# UV_LED_SH01.net
KiCad netlist of a schematic drawn in EasyEDA
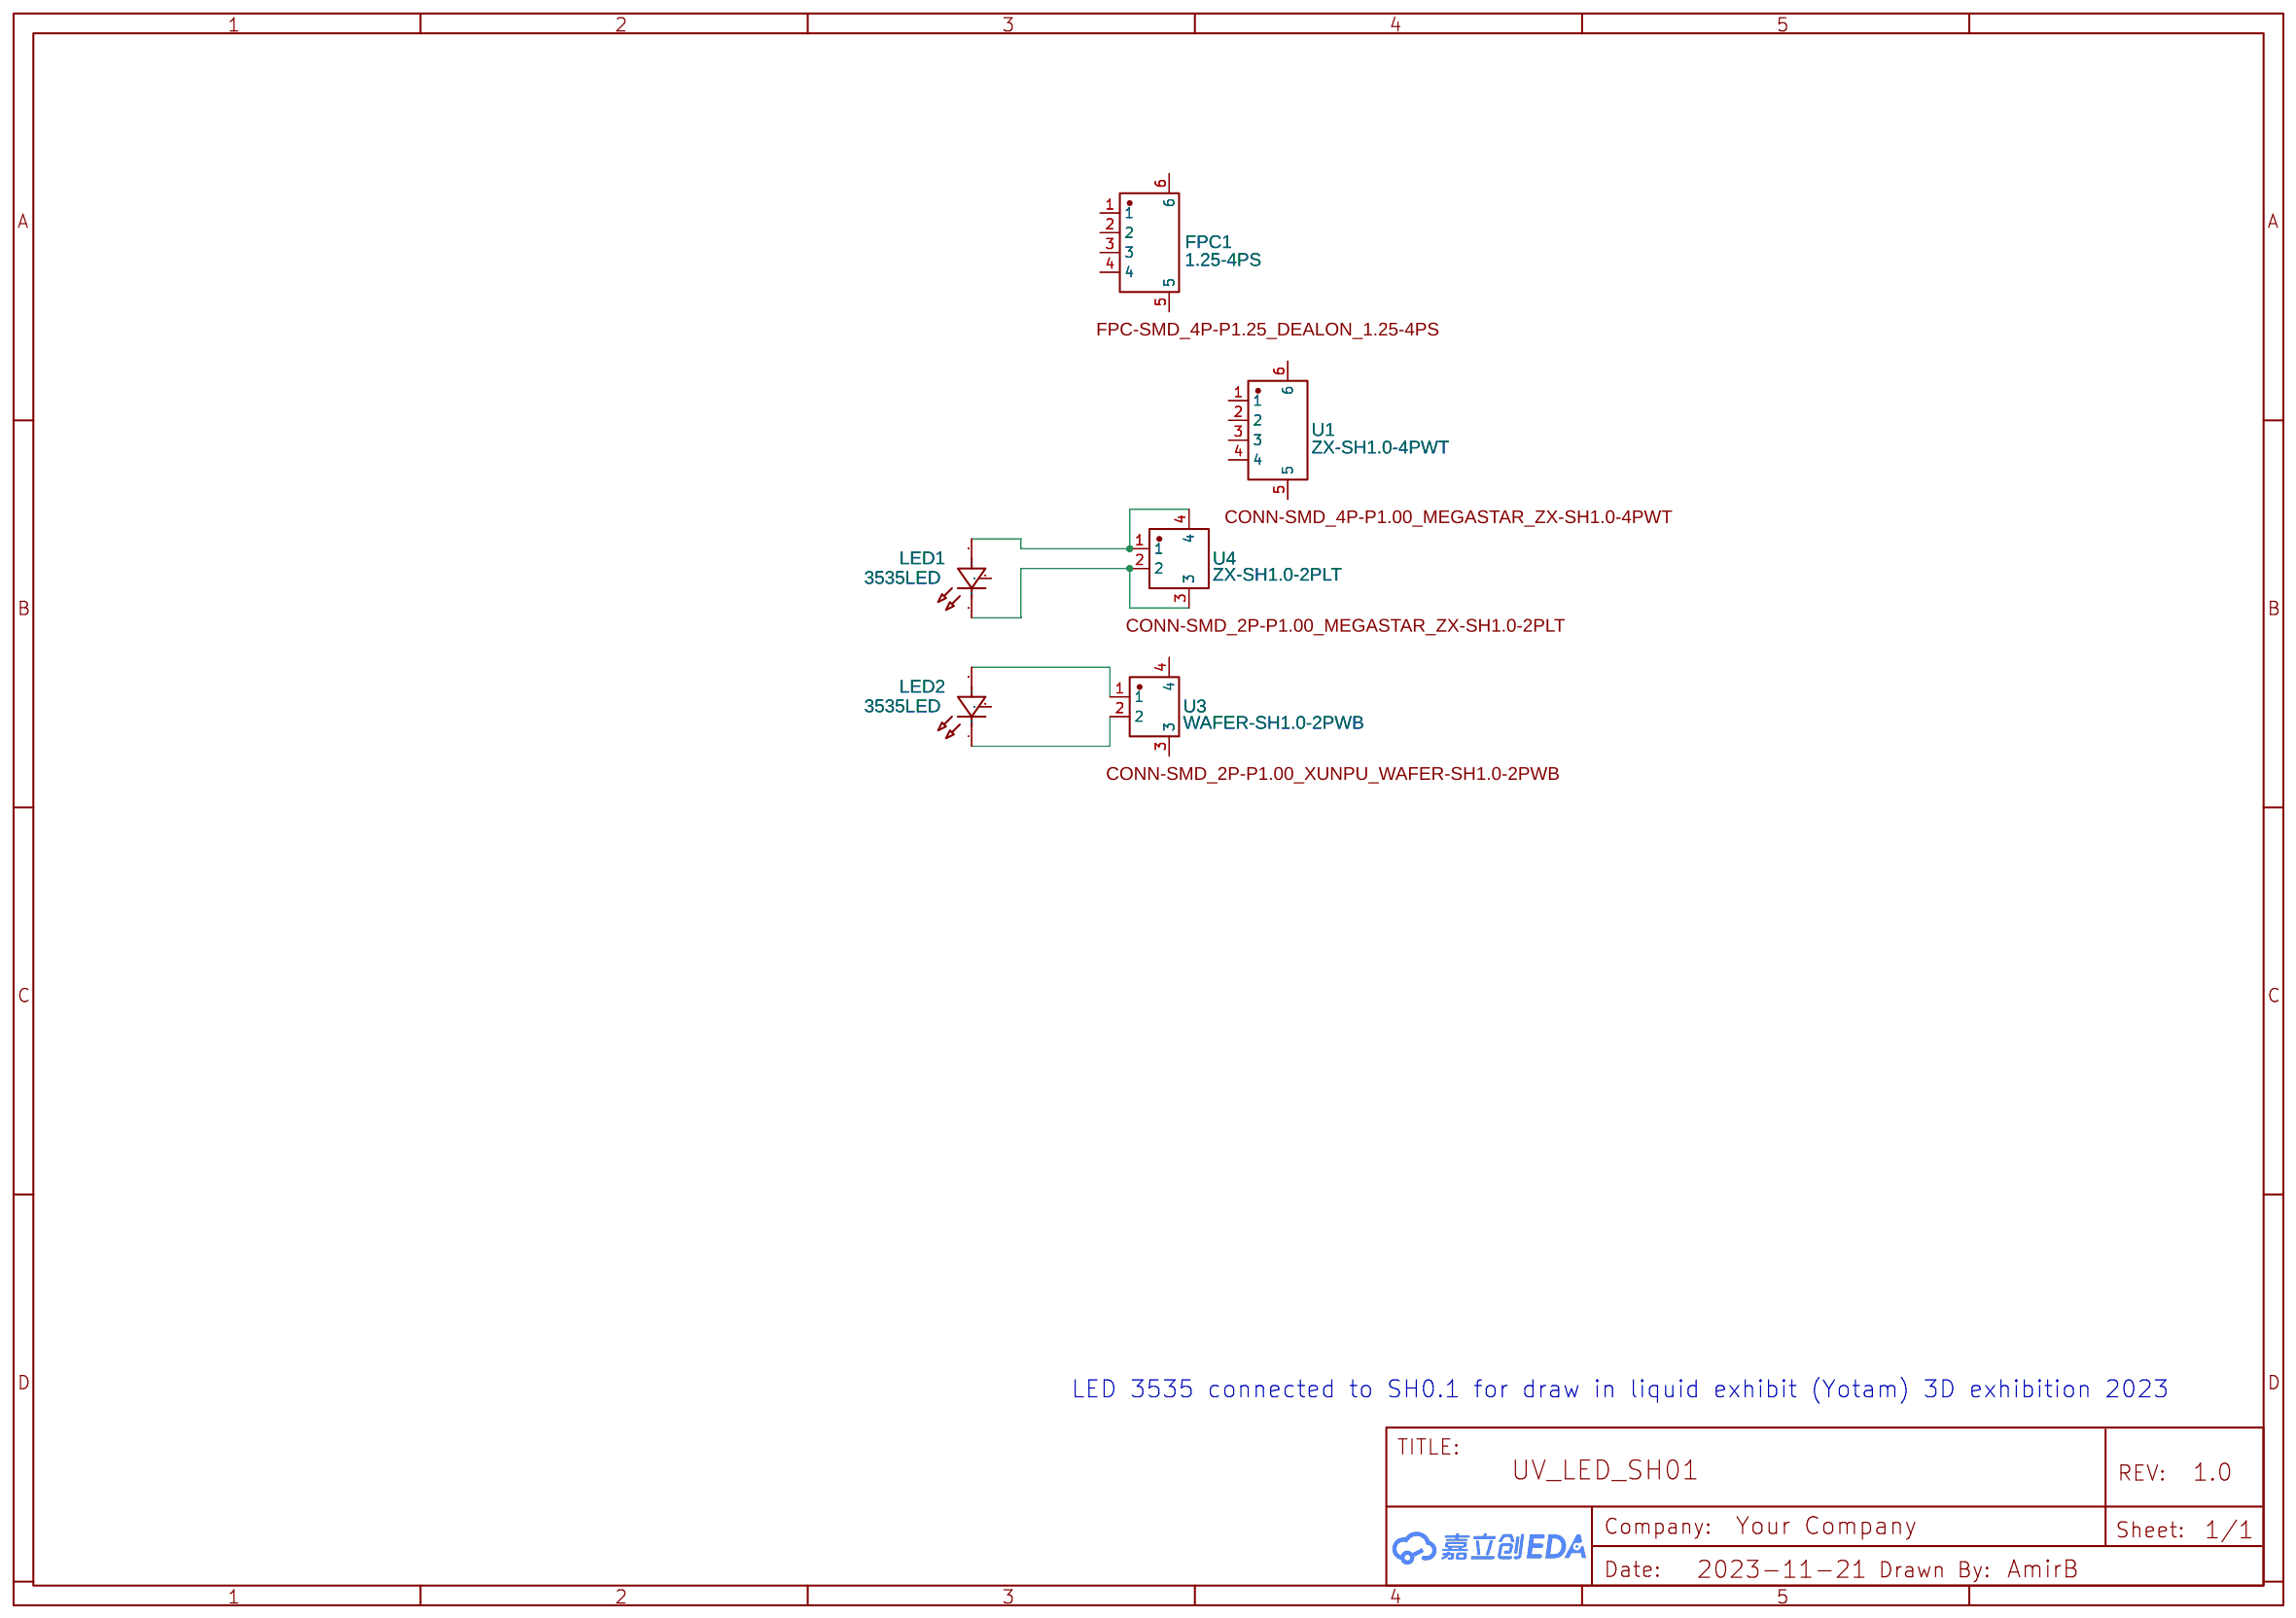
[diagram p0: schematic sheet]

(export (version "E")
  (design (tool "Eeschema 10.0.6"))
  (components
    (comp (ref "FPC1")
      (value "1.25-4PS")
      (fields (field (name "Manufacturer") "DEALON(德艺隆)"))
      (libsource (lib "") (part "1.25-4PS"))
    )
    (comp (ref "LED1")
      (value "3535LED")
      (fields
        (field (name "BOM_Manufacturer Part") "M3535N1UVS8U06-365nm")
        (field (name "BOM_Supplier Part") "C2833503")
      )
      (libsource (lib "") (part "M3535N1UVS8U06-365NM"))
    )
    (comp (ref "LED2")
      (value "3535LED")
      (fields
        (field (name "BOM_Manufacturer Part") "M3535N1UVS8U06-365nm")
        (field (name "BOM_Supplier Part") "C2833503")
      )
      (libsource (lib "") (part "M3535N1UVS8U06-365NM"))
    )
    (comp (ref "U1")
      (value "ZX-SH1.0-4PWT")
      (fields (field (name "Manufacturer") "Megastar(兆星)"))
      (libsource (lib "") (part "ZX-SH1.0-4PWT"))
    )
    (comp (ref "U3")
      (value "WAFER-SH1.0-2PWB")
      (fields (field (name "Manufacturer") "XUNPU(讯普)"))
      (libsource (lib "") (part "WAFER-SH1.0-2PWB"))
    )
    (comp (ref "U4")
      (value "ZX-SH1.0-2PLT")
      (fields (field (name "Manufacturer") "Megastar(兆星)"))
      (libsource (lib "") (part "ZX-SH1.0-2PLT"))
    )
  )
  (nets
    (net (code "1") (name "Net-(LED1-A)") (class "Default")
      (node (ref "LED1") (pin "2") (pinfunction "A_2") (pintype "unspecified"))
      (node (ref "U4") (pin "1") (pinfunction "1_1") (pintype "unspecified"))
      (node (ref "U4") (pin "4") (pinfunction "4_4") (pintype "unspecified"))
    )
    (net (code "2") (name "Net-(LED1-K)") (class "Default")
      (node (ref "LED1") (pin "1") (pinfunction "K_1") (pintype "unspecified"))
      (node (ref "U4") (pin "2") (pinfunction "2_2") (pintype "unspecified"))
      (node (ref "U4") (pin "3") (pinfunction "3_3") (pintype "unspecified"))
    )
    (net (code "3") (name "Net-(LED2-A)") (class "Default")
      (node (ref "LED2") (pin "2") (pinfunction "A_2") (pintype "unspecified"))
      (node (ref "U3") (pin "1") (pinfunction "1_1") (pintype "unspecified"))
    )
    (net (code "4") (name "Net-(LED2-K)") (class "Default")
      (node (ref "LED2") (pin "1") (pinfunction "K_1") (pintype "unspecified"))
      (node (ref "U3") (pin "2") (pinfunction "2_2") (pintype "unspecified"))
    )
    (net (code "5") (name "unconnected-(FPC1-Pad1)") (class "Default")
      (node (ref "FPC1") (pin "1") (pinfunction "1_1") (pintype "unspecified"))
    )
    (net (code "6") (name "unconnected-(FPC1-Pad2)") (class "Default")
      (node (ref "FPC1") (pin "2") (pinfunction "2_2") (pintype "unspecified"))
    )
    (net (code "7") (name "unconnected-(FPC1-Pad3)") (class "Default")
      (node (ref "FPC1") (pin "3") (pinfunction "3_3") (pintype "unspecified"))
    )
    (net (code "8") (name "unconnected-(FPC1-Pad4)") (class "Default")
      (node (ref "FPC1") (pin "4") (pinfunction "4_4") (pintype "unspecified"))
    )
    (net (code "9") (name "unconnected-(FPC1-Pad5)") (class "Default")
      (node (ref "FPC1") (pin "5") (pinfunction "5_5") (pintype "unspecified"))
    )
    (net (code "10") (name "unconnected-(FPC1-Pad6)") (class "Default")
      (node (ref "FPC1") (pin "6") (pinfunction "6_6") (pintype "unspecified"))
    )
    (net (code "11") (name "unconnected-(LED1-Pad3)") (class "Default")
      (node (ref "LED1") (pin "3") (pinfunction "3_3") (pintype "unspecified"))
    )
    (net (code "12") (name "unconnected-(LED2-Pad3)") (class "Default")
      (node (ref "LED2") (pin "3") (pinfunction "3_3") (pintype "unspecified"))
    )
    (net (code "13") (name "unconnected-(U1-Pad1)") (class "Default")
      (node (ref "U1") (pin "1") (pinfunction "1_1") (pintype "unspecified"))
    )
    (net (code "14") (name "unconnected-(U1-Pad2)") (class "Default")
      (node (ref "U1") (pin "2") (pinfunction "2_2") (pintype "unspecified"))
    )
    (net (code "15") (name "unconnected-(U1-Pad3)") (class "Default")
      (node (ref "U1") (pin "3") (pinfunction "3_3") (pintype "unspecified"))
    )
    (net (code "16") (name "unconnected-(U1-Pad4)") (class "Default")
      (node (ref "U1") (pin "4") (pinfunction "4_4") (pintype "unspecified"))
    )
    (net (code "17") (name "unconnected-(U1-Pad5)") (class "Default")
      (node (ref "U1") (pin "5") (pinfunction "5_5") (pintype "unspecified"))
    )
    (net (code "18") (name "unconnected-(U1-Pad6)") (class "Default")
      (node (ref "U1") (pin "6") (pinfunction "6_6") (pintype "unspecified"))
    )
    (net (code "19") (name "unconnected-(U3-Pad3)") (class "Default")
      (node (ref "U3") (pin "3") (pinfunction "3_3") (pintype "unspecified"))
    )
    (net (code "20") (name "unconnected-(U3-Pad4)") (class "Default")
      (node (ref "U3") (pin "4") (pinfunction "4_4") (pintype "unspecified"))
    )
  )
)
